# Schematic_page3.net
KiCad netlist of a schematic drawn in Altium Designer
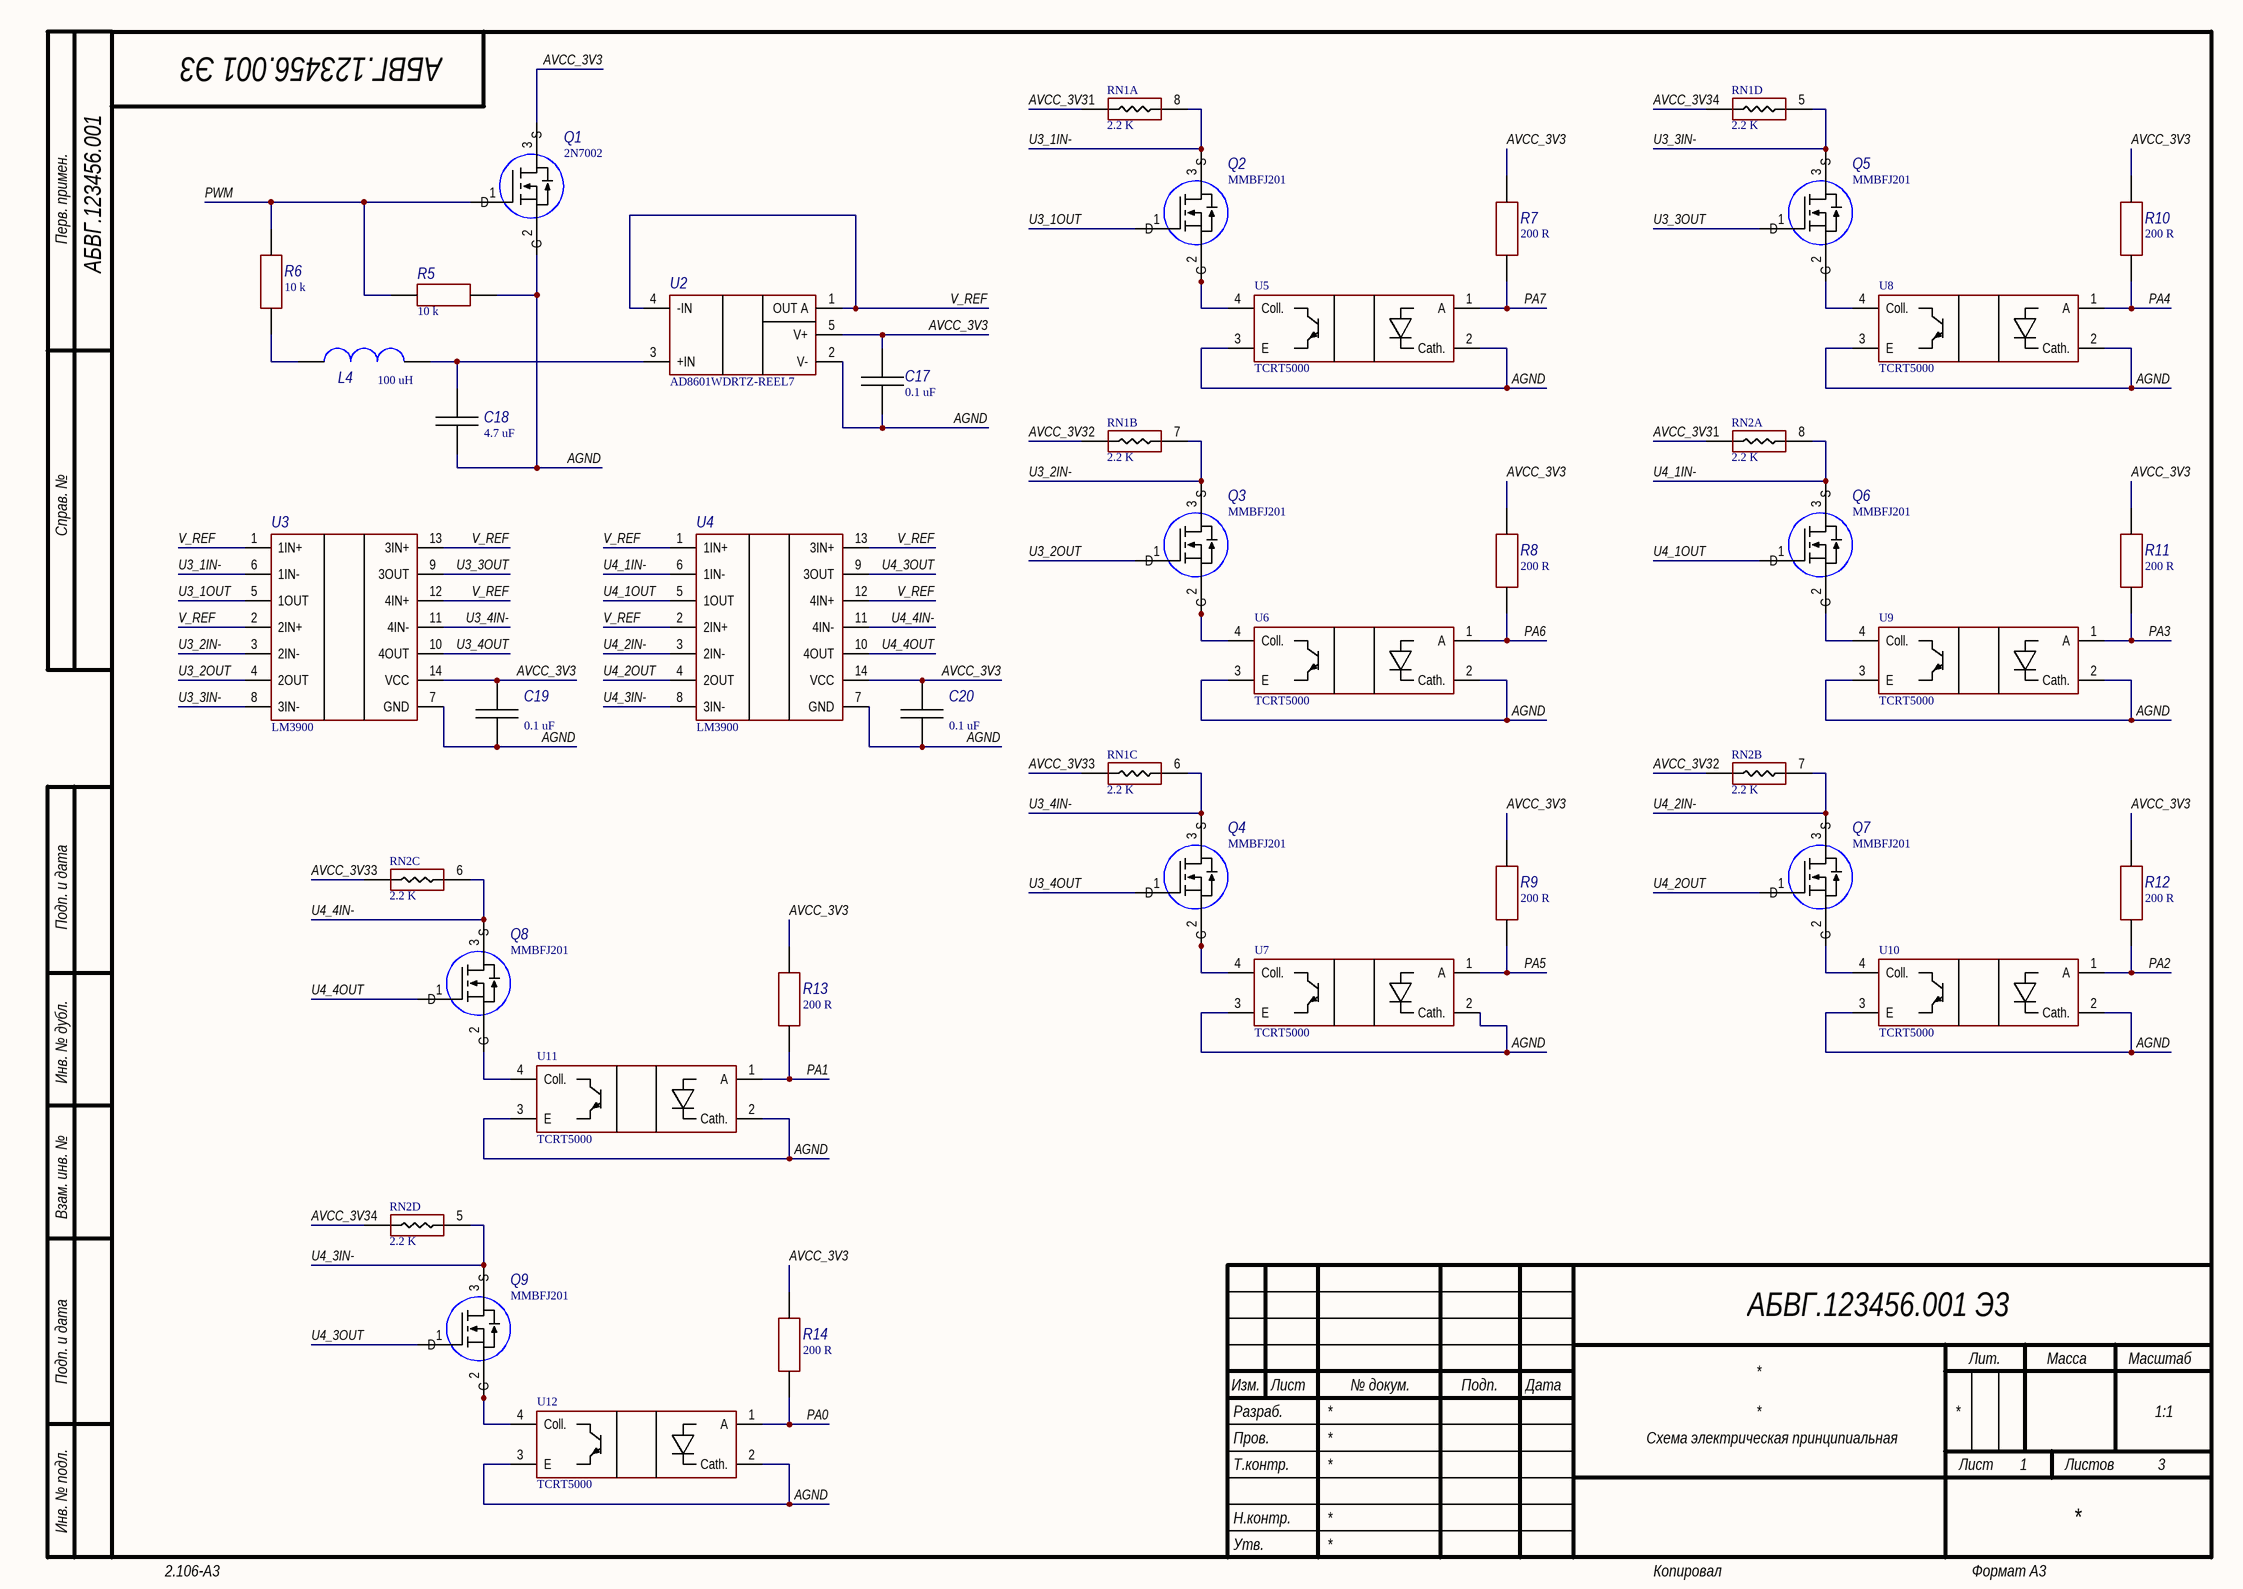
[diagram p0: Schematic_page3.SchDoc]

(export (version "E")
  (design (tool "Eeschema 10.0.6"))
  (components
    (comp (ref "C17")
      (value "0.1 uF")
      (footprint "C0603")
      (libsource (lib "Linalance_lib") (part "Capasitor"))
    )
    (comp (ref "C18")
      (value "4.7 uF")
      (footprint "C0603")
      (libsource (lib "Linalance_lib") (part "Capasitor"))
    )
    (comp (ref "C19")
      (value "0.1 uF")
      (footprint "C0603")
      (libsource (lib "Linalance_lib") (part "Capasitor"))
    )
    (comp (ref "C20")
      (value "0.1 uF")
      (footprint "C0603")
      (libsource (lib "Linalance_lib") (part "Capasitor"))
    )
    (comp (ref "L4")
      (value "100 uH")
      (footprint "IND1206")
      (libsource (lib "Linalance_lib") (part "Inductivity"))
    )
    (comp (ref "Q1")
      (value "2N7002")
      (footprint "SOT-23-3")
      (description "MOSFET N-Channel 60V 115mA (Ta) 200mW (Ta) Surface Mount SOT-23 (TO-236AB)")
      (fields (field (name "MANUFACTURER") "ON Semiconductor"))
      (libsource (lib "Linalance_lib") (part "2N7002"))
    )
    (comp (ref "Q2")
      (value "MMBFJ201")
      (footprint "SOT-23-3")
      (description "JFET N-Channel 40V 350mW Surface Mount SOT-23-3")
      (libsource (lib "Linalance_lib") (part "MMBFJ201"))
    )
    (comp (ref "Q3")
      (value "MMBFJ201")
      (footprint "SOT-23-3")
      (description "JFET N-Channel 40V 350mW Surface Mount SOT-23-3")
      (libsource (lib "Linalance_lib") (part "MMBFJ201"))
    )
    (comp (ref "Q4")
      (value "MMBFJ201")
      (footprint "SOT-23-3")
      (description "JFET N-Channel 40V 350mW Surface Mount SOT-23-3")
      (libsource (lib "Linalance_lib") (part "MMBFJ201"))
    )
    (comp (ref "Q5")
      (value "MMBFJ201")
      (footprint "SOT-23-3")
      (description "JFET N-Channel 40V 350mW Surface Mount SOT-23-3")
      (libsource (lib "Linalance_lib") (part "MMBFJ201"))
    )
    (comp (ref "Q6")
      (value "MMBFJ201")
      (footprint "SOT-23-3")
      (description "JFET N-Channel 40V 350mW Surface Mount SOT-23-3")
      (libsource (lib "Linalance_lib") (part "MMBFJ201"))
    )
    (comp (ref "Q7")
      (value "MMBFJ201")
      (footprint "SOT-23-3")
      (description "JFET N-Channel 40V 350mW Surface Mount SOT-23-3")
      (libsource (lib "Linalance_lib") (part "MMBFJ201"))
    )
    (comp (ref "Q8")
      (value "MMBFJ201")
      (footprint "SOT-23-3")
      (description "JFET N-Channel 40V 350mW Surface Mount SOT-23-3")
      (libsource (lib "Linalance_lib") (part "MMBFJ201"))
    )
    (comp (ref "Q9")
      (value "MMBFJ201")
      (footprint "SOT-23-3")
      (description "JFET N-Channel 40V 350mW Surface Mount SOT-23-3")
      (libsource (lib "Linalance_lib") (part "MMBFJ201"))
    )
    (comp (ref "R5") (value "10 k") (footprint "R0603") (libsource (lib "") (part "Resistor_1")))
    (comp (ref "R6") (value "10 k") (footprint "R0603") (libsource (lib "Linalance_lib") (part "Resistor")))
    (comp (ref "R7") (value "200 R") (footprint "R0603") (libsource (lib "Linalance_lib") (part "Resistor")))
    (comp (ref "R8") (value "200 R") (footprint "R0603") (libsource (lib "Linalance_lib") (part "Resistor")))
    (comp (ref "R9") (value "200 R") (footprint "R0603") (libsource (lib "Linalance_lib") (part "Resistor")))
    (comp (ref "R10") (value "200 R") (footprint "R0603") (libsource (lib "Linalance_lib") (part "Resistor")))
    (comp (ref "R11") (value "200 R") (footprint "R0603") (libsource (lib "Linalance_lib") (part "Resistor")))
    (comp (ref "R12") (value "200 R") (footprint "R0603") (libsource (lib "Linalance_lib") (part "Resistor")))
    (comp (ref "R13") (value "200 R") (footprint "R0603") (libsource (lib "Linalance_lib") (part "Resistor")))
    (comp (ref "R14") (value "200 R") (footprint "R0603") (libsource (lib "Linalance_lib") (part "Resistor")))
    (comp (ref "RN1")
      (value "2.2 K")
      (footprint "RN_YC164-JR-072K2L")
      (libsource (lib "Linalance_lib") (part "Resistor Network"))
    )
    (comp (ref "RN2")
      (value "2.2 K")
      (footprint "RN_YC164-JR-072K2L")
      (libsource (lib "Linalance_lib") (part "Resistor Network"))
    )
    (comp (ref "U2")
      (value "AD8601WDRTZ-REEL7")
      (footprint "SOT-23-5")
      (description "IC OPAMP GP 1 CIRCUIT SOT23-5")
      (fields (field (name "MANUFACTURER") "Analog Devices Inc."))
      (libsource (lib "Linalance_lib") (part "AD8601"))
    )
    (comp (ref "U3")
      (value "LM3900")
      (footprint "SOIC-14")
      (description "IC OPAMP GP 4 CIRCUIT 14SOIC")
      (fields (field (name "MANUFACTURER") "Texas Instruments"))
      (libsource (lib "Linalance_lib") (part "LM3900"))
    )
    (comp (ref "U4")
      (value "LM3900")
      (footprint "SOIC-14")
      (description "IC OPAMP GP 4 CIRCUIT 14SOIC")
      (fields (field (name "MANUFACTURER") "Texas Instruments"))
      (libsource (lib "Linalance_lib") (part "LM3900"))
    )
    (comp (ref "U5")
      (value "TCRT5000")
      (footprint "TCRT5000")
      (description "SENSOR OPTO TRANS 15MM REFL PCB")
      (fields (field (name "MANUFACTURER") "Vishay Semiconductor Opto Division"))
      (libsource (lib "Linalance_lib") (part "TCRT5000"))
    )
    (comp (ref "U6")
      (value "TCRT5000")
      (footprint "TCRT5000")
      (description "SENSOR OPTO TRANS 15MM REFL PCB")
      (fields (field (name "MANUFACTURER") "Vishay Semiconductor Opto Division"))
      (libsource (lib "Linalance_lib") (part "TCRT5000"))
    )
    (comp (ref "U7")
      (value "TCRT5000")
      (footprint "TCRT5000")
      (description "SENSOR OPTO TRANS 15MM REFL PCB")
      (fields (field (name "MANUFACTURER") "Vishay Semiconductor Opto Division"))
      (libsource (lib "Linalance_lib") (part "TCRT5000"))
    )
    (comp (ref "U8")
      (value "TCRT5000")
      (footprint "TCRT5000")
      (description "SENSOR OPTO TRANS 15MM REFL PCB")
      (fields (field (name "MANUFACTURER") "Vishay Semiconductor Opto Division"))
      (libsource (lib "Linalance_lib") (part "TCRT5000"))
    )
    (comp (ref "U9")
      (value "TCRT5000")
      (footprint "TCRT5000")
      (description "SENSOR OPTO TRANS 15MM REFL PCB")
      (fields (field (name "MANUFACTURER") "Vishay Semiconductor Opto Division"))
      (libsource (lib "Linalance_lib") (part "TCRT5000"))
    )
    (comp (ref "U10")
      (value "TCRT5000")
      (footprint "TCRT5000")
      (description "SENSOR OPTO TRANS 15MM REFL PCB")
      (fields (field (name "MANUFACTURER") "Vishay Semiconductor Opto Division"))
      (libsource (lib "Linalance_lib") (part "TCRT5000"))
    )
    (comp (ref "U11")
      (value "TCRT5000")
      (footprint "TCRT5000")
      (description "SENSOR OPTO TRANS 15MM REFL PCB")
      (fields (field (name "MANUFACTURER") "Vishay Semiconductor Opto Division"))
      (libsource (lib "Linalance_lib") (part "TCRT5000"))
    )
    (comp (ref "U12")
      (value "TCRT5000")
      (footprint "TCRT5000")
      (description "SENSOR OPTO TRANS 15MM REFL PCB")
      (fields (field (name "MANUFACTURER") "Vishay Semiconductor Opto Division"))
      (libsource (lib "Linalance_lib") (part "TCRT5000"))
    )
  )
  (nets
    (net (code "1") (name "/AGND") (class "Default")
      (node (ref "C17") (pin "2") (pintype "passive"))
      (node (ref "C18") (pin "2") (pintype "passive"))
      (node (ref "C19") (pin "2") (pintype "passive"))
      (node (ref "C20") (pin "2") (pintype "passive"))
      (node (ref "Q1") (pin "2") (pinfunction "G_2") (pintype "passive"))
      (node (ref "R5") (pin "2") (pintype "passive"))
      (node (ref "U10") (pin "2") (pinfunction "Cath._2") (pintype "passive"))
      (node (ref "U10") (pin "3") (pinfunction "E_3") (pintype "passive"))
      (node (ref "U11") (pin "2") (pinfunction "Cath._2") (pintype "passive"))
      (node (ref "U11") (pin "3") (pinfunction "E_3") (pintype "passive"))
      (node (ref "U12") (pin "2") (pinfunction "Cath._2") (pintype "passive"))
      (node (ref "U12") (pin "3") (pinfunction "E_3") (pintype "passive"))
      (node (ref "U2") (pin "2") (pinfunction "V-_2") (pintype "passive"))
      (node (ref "U3") (pin "7") (pinfunction "GND_7") (pintype "passive"))
      (node (ref "U4") (pin "7") (pinfunction "GND_7") (pintype "passive"))
      (node (ref "U5") (pin "2") (pinfunction "Cath._2") (pintype "passive"))
      (node (ref "U5") (pin "3") (pinfunction "E_3") (pintype "passive"))
      (node (ref "U6") (pin "2") (pinfunction "Cath._2") (pintype "passive"))
      (node (ref "U6") (pin "3") (pinfunction "E_3") (pintype "passive"))
      (node (ref "U7") (pin "2") (pinfunction "Cath._2") (pintype "passive"))
      (node (ref "U7") (pin "3") (pinfunction "E_3") (pintype "passive"))
      (node (ref "U8") (pin "2") (pinfunction "Cath._2") (pintype "passive"))
      (node (ref "U8") (pin "3") (pinfunction "E_3") (pintype "passive"))
      (node (ref "U9") (pin "2") (pinfunction "Cath._2") (pintype "passive"))
      (node (ref "U9") (pin "3") (pinfunction "E_3") (pintype "passive"))
    )
    (net (code "2") (name "/AVCC_3V3") (class "Default")
      (node (ref "C17") (pin "1") (pintype "passive"))
      (node (ref "C19") (pin "1") (pintype "passive"))
      (node (ref "C20") (pin "1") (pintype "passive"))
      (node (ref "Q1") (pin "3") (pinfunction "S_3") (pintype "passive"))
      (node (ref "R10") (pin "2") (pintype "passive"))
      (node (ref "R11") (pin "2") (pintype "passive"))
      (node (ref "R12") (pin "2") (pintype "passive"))
      (node (ref "R13") (pin "2") (pintype "passive"))
      (node (ref "R14") (pin "2") (pintype "passive"))
      (node (ref "R7") (pin "2") (pintype "passive"))
      (node (ref "R8") (pin "2") (pintype "passive"))
      (node (ref "R9") (pin "2") (pintype "passive"))
      (node (ref "RN1") (pin "1") (pintype "passive"))
      (node (ref "RN1") (pin "2") (pintype "passive"))
      (node (ref "RN1") (pin "3") (pintype "passive"))
      (node (ref "RN1") (pin "4") (pintype "passive"))
      (node (ref "RN2") (pin "1") (pintype "passive"))
      (node (ref "RN2") (pin "2") (pintype "passive"))
      (node (ref "RN2") (pin "3") (pintype "passive"))
      (node (ref "RN2") (pin "4") (pintype "passive"))
      (node (ref "U2") (pin "5") (pinfunction "V+_5") (pintype "passive"))
      (node (ref "U3") (pin "14") (pinfunction "VCC_14") (pintype "passive"))
      (node (ref "U4") (pin "14") (pinfunction "VCC_14") (pintype "passive"))
    )
    (net (code "3") (name "/PA0") (class "Default")
      (node (ref "R14") (pin "1") (pintype "passive"))
      (node (ref "U12") (pin "1") (pinfunction "A_1") (pintype "passive"))
    )
    (net (code "4") (name "/PA1") (class "Default")
      (node (ref "R13") (pin "1") (pintype "passive"))
      (node (ref "U11") (pin "1") (pinfunction "A_1") (pintype "passive"))
    )
    (net (code "5") (name "/PA2") (class "Default")
      (node (ref "R12") (pin "1") (pintype "passive"))
      (node (ref "U10") (pin "1") (pinfunction "A_1") (pintype "passive"))
    )
    (net (code "6") (name "/PA3") (class "Default")
      (node (ref "R11") (pin "1") (pintype "passive"))
      (node (ref "U9") (pin "1") (pinfunction "A_1") (pintype "passive"))
    )
    (net (code "7") (name "/PA4") (class "Default")
      (node (ref "R10") (pin "1") (pintype "passive"))
      (node (ref "U8") (pin "1") (pinfunction "A_1") (pintype "passive"))
    )
    (net (code "8") (name "/PA5") (class "Default")
      (node (ref "R9") (pin "1") (pintype "passive"))
      (node (ref "U7") (pin "1") (pinfunction "A_1") (pintype "passive"))
    )
    (net (code "9") (name "/PA6") (class "Default")
      (node (ref "R8") (pin "1") (pintype "passive"))
      (node (ref "U6") (pin "1") (pinfunction "A_1") (pintype "passive"))
    )
    (net (code "10") (name "/PA7") (class "Default")
      (node (ref "R7") (pin "1") (pintype "passive"))
      (node (ref "U5") (pin "1") (pinfunction "A_1") (pintype "passive"))
    )
    (net (code "11") (name "/PWM") (class "Default")
      (node (ref "Q1") (pin "1") (pinfunction "D_1") (pintype "passive"))
      (node (ref "R5") (pin "1") (pintype "passive"))
      (node (ref "R6") (pin "2") (pintype "passive"))
    )
    (net (code "12") (name "/U3_1IN-") (class "Default")
      (node (ref "Q2") (pin "3") (pinfunction "S_3") (pintype "passive"))
      (node (ref "RN1") (pin "8") (pintype "passive"))
      (node (ref "U3") (pin "6") (pinfunction "1IN-_6") (pintype "passive"))
    )
    (net (code "13") (name "/U3_1OUT") (class "Default")
      (node (ref "Q2") (pin "1") (pinfunction "D_1") (pintype "passive"))
      (node (ref "U3") (pin "5") (pinfunction "1OUT_5") (pintype "passive"))
    )
    (net (code "14") (name "/U3_2IN-") (class "Default")
      (node (ref "Q3") (pin "3") (pinfunction "S_3") (pintype "passive"))
      (node (ref "RN1") (pin "7") (pintype "passive"))
      (node (ref "U3") (pin "3") (pinfunction "2IN-_3") (pintype "passive"))
    )
    (net (code "15") (name "/U3_2OUT") (class "Default")
      (node (ref "Q3") (pin "1") (pinfunction "D_1") (pintype "passive"))
      (node (ref "U3") (pin "4") (pinfunction "2OUT_4") (pintype "passive"))
    )
    (net (code "16") (name "/U3_3IN-") (class "Default")
      (node (ref "Q5") (pin "3") (pinfunction "S_3") (pintype "passive"))
      (node (ref "RN1") (pin "5") (pintype "passive"))
      (node (ref "U3") (pin "8") (pinfunction "3IN-_8") (pintype "passive"))
    )
    (net (code "17") (name "/U3_3OUT") (class "Default")
      (node (ref "Q5") (pin "1") (pinfunction "D_1") (pintype "passive"))
      (node (ref "U3") (pin "9") (pinfunction "3OUT_9") (pintype "passive"))
    )
    (net (code "18") (name "/U3_4IN-") (class "Default")
      (node (ref "Q4") (pin "3") (pinfunction "S_3") (pintype "passive"))
      (node (ref "RN1") (pin "6") (pintype "passive"))
      (node (ref "U3") (pin "11") (pinfunction "4IN-_11") (pintype "passive"))
    )
    (net (code "19") (name "/U3_4OUT") (class "Default")
      (node (ref "Q4") (pin "1") (pinfunction "D_1") (pintype "passive"))
      (node (ref "U3") (pin "10") (pinfunction "4OUT_10") (pintype "passive"))
    )
    (net (code "20") (name "/U4_1IN-") (class "Default")
      (node (ref "Q6") (pin "3") (pinfunction "S_3") (pintype "passive"))
      (node (ref "RN2") (pin "8") (pintype "passive"))
      (node (ref "U4") (pin "6") (pinfunction "1IN-_6") (pintype "passive"))
    )
    (net (code "21") (name "/U4_1OUT") (class "Default")
      (node (ref "Q6") (pin "1") (pinfunction "D_1") (pintype "passive"))
      (node (ref "U4") (pin "5") (pinfunction "1OUT_5") (pintype "passive"))
    )
    (net (code "22") (name "/U4_2IN-") (class "Default")
      (node (ref "Q7") (pin "3") (pinfunction "S_3") (pintype "passive"))
      (node (ref "RN2") (pin "7") (pintype "passive"))
      (node (ref "U4") (pin "3") (pinfunction "2IN-_3") (pintype "passive"))
    )
    (net (code "23") (name "/U4_2OUT") (class "Default")
      (node (ref "Q7") (pin "1") (pinfunction "D_1") (pintype "passive"))
      (node (ref "U4") (pin "4") (pinfunction "2OUT_4") (pintype "passive"))
    )
    (net (code "24") (name "/U4_3IN-") (class "Default")
      (node (ref "Q9") (pin "3") (pinfunction "S_3") (pintype "passive"))
      (node (ref "RN2") (pin "5") (pintype "passive"))
      (node (ref "U4") (pin "8") (pinfunction "3IN-_8") (pintype "passive"))
    )
    (net (code "25") (name "/U4_3OUT") (class "Default")
      (node (ref "Q9") (pin "1") (pinfunction "D_1") (pintype "passive"))
      (node (ref "U4") (pin "9") (pinfunction "3OUT_9") (pintype "passive"))
    )
    (net (code "26") (name "/U4_4IN-") (class "Default")
      (node (ref "Q8") (pin "3") (pinfunction "S_3") (pintype "passive"))
      (node (ref "RN2") (pin "6") (pintype "passive"))
      (node (ref "U4") (pin "11") (pinfunction "4IN-_11") (pintype "passive"))
    )
    (net (code "27") (name "/U4_4OUT") (class "Default")
      (node (ref "Q8") (pin "1") (pinfunction "D_1") (pintype "passive"))
      (node (ref "U4") (pin "10") (pinfunction "4OUT_10") (pintype "passive"))
    )
    (net (code "28") (name "/V_REF") (class "Default")
      (node (ref "U2") (pin "1") (pinfunction "OUT_A_1") (pintype "passive"))
      (node (ref "U2") (pin "4") (pinfunction "-IN_4") (pintype "passive"))
      (node (ref "U3") (pin "1") (pinfunction "1IN+_1") (pintype "passive"))
      (node (ref "U3") (pin "12") (pinfunction "4IN+_12") (pintype "passive"))
      (node (ref "U3") (pin "13") (pinfunction "3IN+_13") (pintype "passive"))
      (node (ref "U3") (pin "2") (pinfunction "2IN+_2") (pintype "passive"))
      (node (ref "U4") (pin "1") (pinfunction "1IN+_1") (pintype "passive"))
      (node (ref "U4") (pin "12") (pinfunction "4IN+_12") (pintype "passive"))
      (node (ref "U4") (pin "13") (pinfunction "3IN+_13") (pintype "passive"))
      (node (ref "U4") (pin "2") (pinfunction "2IN+_2") (pintype "passive"))
    )
    (net (code "29") (name "Net-(L4-Pad1)") (class "Default")
      (node (ref "L4") (pin "1") (pintype "passive"))
      (node (ref "R6") (pin "1") (pintype "passive"))
    )
    (net (code "30") (name "Net-(Q2-G)") (class "Default")
      (node (ref "Q2") (pin "2") (pinfunction "G_2") (pintype "passive"))
      (node (ref "U5") (pin "4") (pinfunction "Coll._4") (pintype "passive"))
    )
    (net (code "31") (name "Net-(Q3-G)") (class "Default")
      (node (ref "Q3") (pin "2") (pinfunction "G_2") (pintype "passive"))
      (node (ref "U6") (pin "4") (pinfunction "Coll._4") (pintype "passive"))
    )
    (net (code "32") (name "Net-(Q4-G)") (class "Default")
      (node (ref "Q4") (pin "2") (pinfunction "G_2") (pintype "passive"))
      (node (ref "U7") (pin "4") (pinfunction "Coll._4") (pintype "passive"))
    )
    (net (code "33") (name "Net-(Q5-G)") (class "Default")
      (node (ref "Q5") (pin "2") (pinfunction "G_2") (pintype "passive"))
      (node (ref "U8") (pin "4") (pinfunction "Coll._4") (pintype "passive"))
    )
    (net (code "34") (name "Net-(Q6-G)") (class "Default")
      (node (ref "Q6") (pin "2") (pinfunction "G_2") (pintype "passive"))
      (node (ref "U9") (pin "4") (pinfunction "Coll._4") (pintype "passive"))
    )
    (net (code "35") (name "Net-(Q7-G)") (class "Default")
      (node (ref "Q7") (pin "2") (pinfunction "G_2") (pintype "passive"))
      (node (ref "U10") (pin "4") (pinfunction "Coll._4") (pintype "passive"))
    )
    (net (code "36") (name "Net-(Q8-G)") (class "Default")
      (node (ref "Q8") (pin "2") (pinfunction "G_2") (pintype "passive"))
      (node (ref "U11") (pin "4") (pinfunction "Coll._4") (pintype "passive"))
    )
    (net (code "37") (name "Net-(Q9-G)") (class "Default")
      (node (ref "Q9") (pin "2") (pinfunction "G_2") (pintype "passive"))
      (node (ref "U12") (pin "4") (pinfunction "Coll._4") (pintype "passive"))
    )
    (net (code "38") (name "Net-(U2-+IN)") (class "Default")
      (node (ref "C18") (pin "1") (pintype "passive"))
      (node (ref "L4") (pin "2") (pintype "passive"))
      (node (ref "U2") (pin "3") (pinfunction "+IN_3") (pintype "passive"))
    )
  )
)
